# tally_box.net
KiCad netlist of a schematic drawn in EAGLE
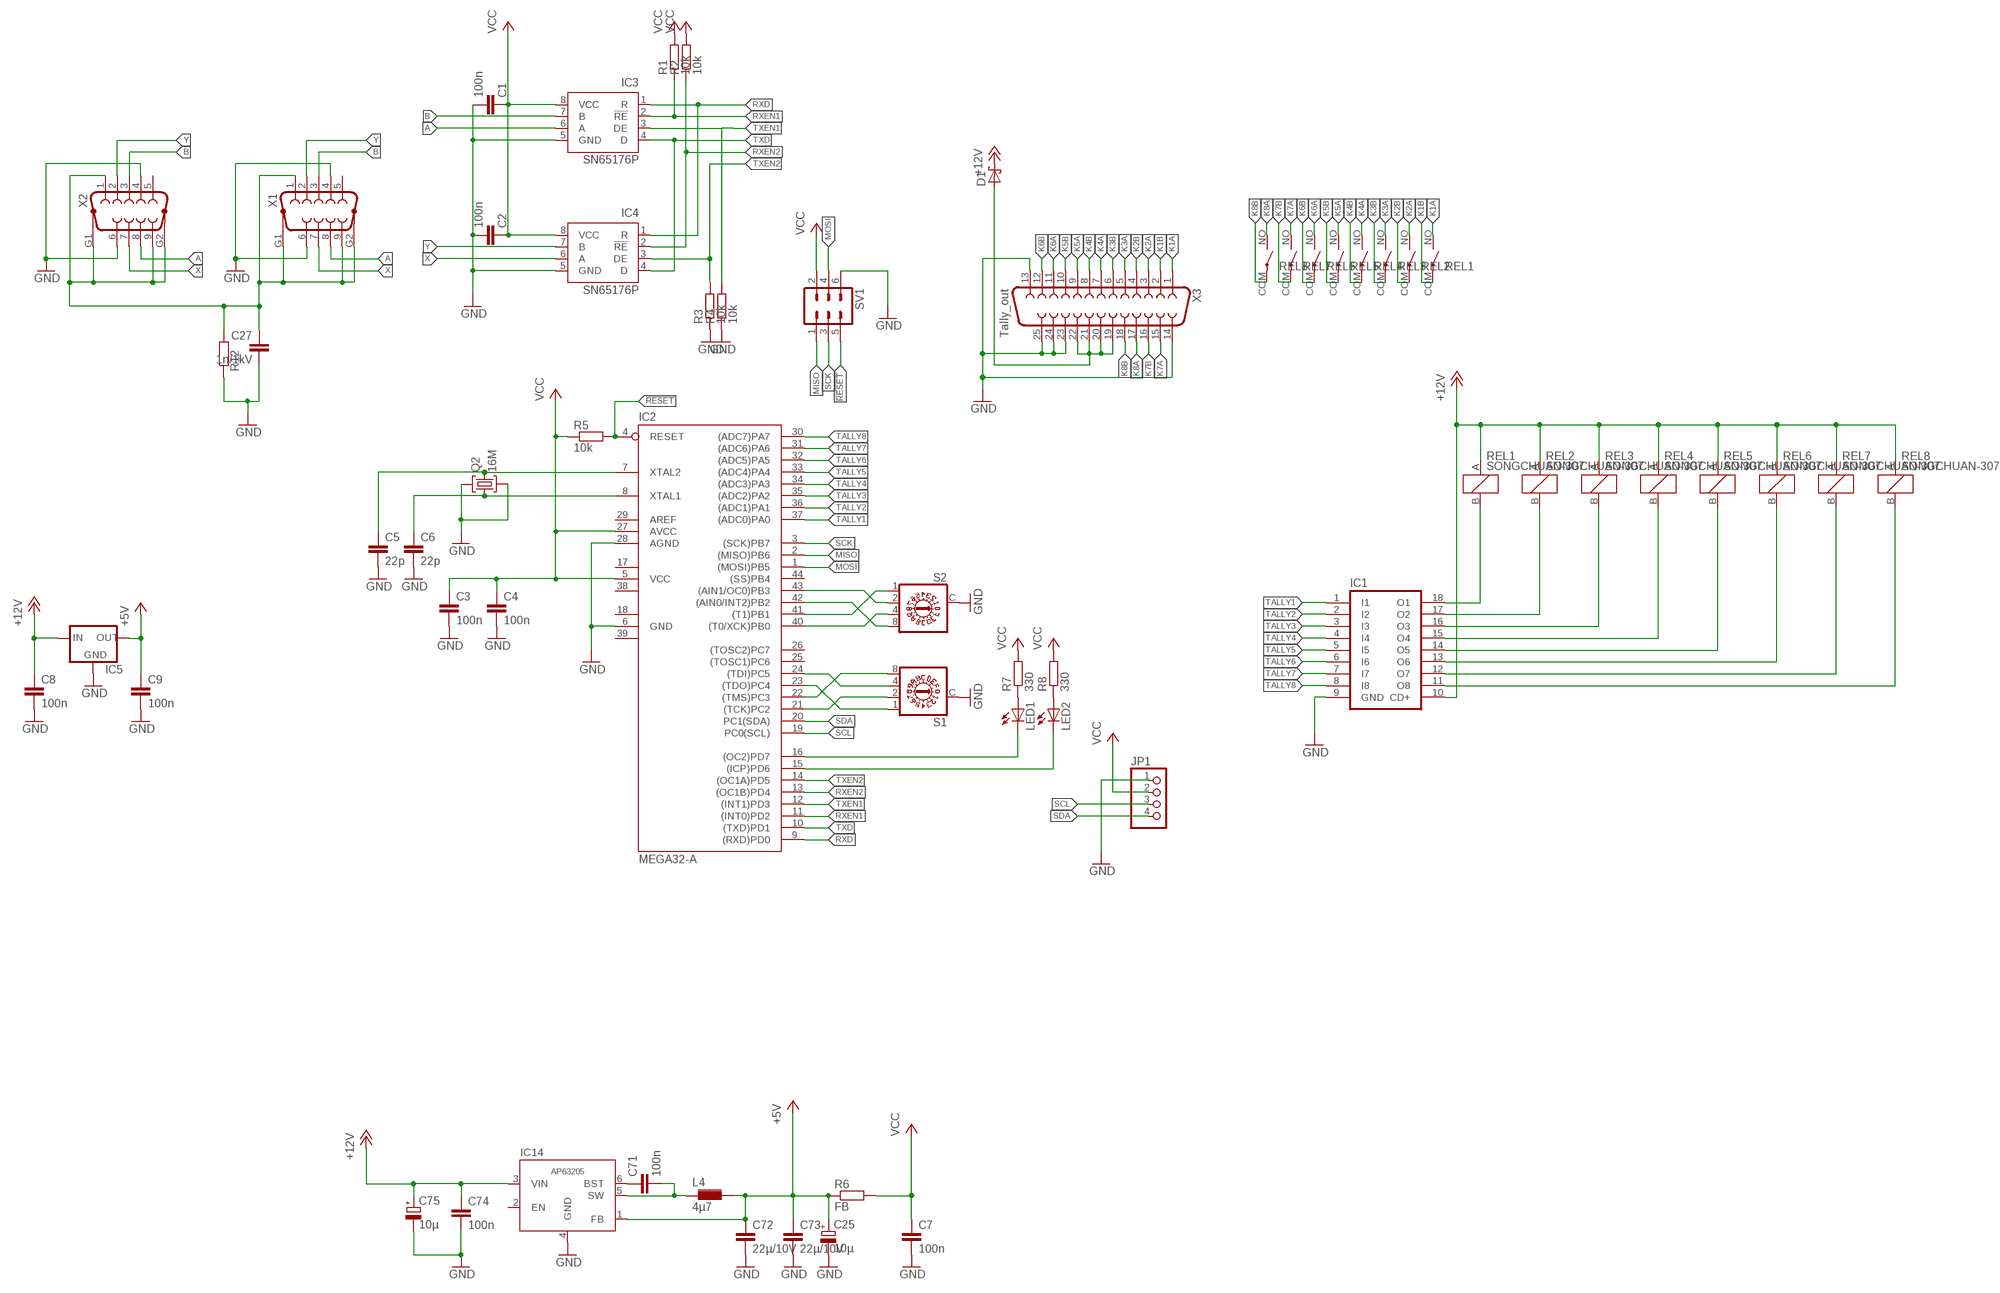
[diagram p0: schematic, sheet 1]

(export (version "E")
  (design (tool "Eeschema 10.0.6"))
  (components
    (comp (ref "C1")
      (value "100n")
      (footprint "eagle-import:C0603")
      (libsource (lib "eagle-import") (part "C-EUC0603"))
    )
    (comp (ref "C2")
      (value "100n")
      (footprint "eagle-import:C0603")
      (libsource (lib "eagle-import") (part "C-EUC0603"))
    )
    (comp (ref "C3")
      (value "100n")
      (footprint "eagle-import:C0603")
      (libsource (lib "eagle-import") (part "C-EUC0603"))
    )
    (comp (ref "C4")
      (value "100n")
      (footprint "eagle-import:C0603")
      (libsource (lib "eagle-import") (part "C-EUC0603"))
    )
    (comp (ref "C5")
      (value "22p")
      (footprint "eagle-import:C0603")
      (libsource (lib "eagle-import") (part "C-EUC0603"))
    )
    (comp (ref "C6")
      (value "22p")
      (footprint "eagle-import:C0603")
      (libsource (lib "eagle-import") (part "C-EUC0603"))
    )
    (comp (ref "C7")
      (value "100n")
      (footprint "eagle-import:C0603")
      (libsource (lib "eagle-import") (part "C-EUC0603"))
    )
    (comp (ref "C8")
      (value "100n")
      (footprint "eagle-import:C0805")
      (libsource (lib "eagle-import") (part "C-EUC0805"))
    )
    (comp (ref "C9")
      (value "100n")
      (footprint "eagle-import:C0805")
      (libsource (lib "eagle-import") (part "C-EUC0805"))
    )
    (comp (ref "C25")
      (value "10µ")
      (footprint "eagle-import:PANASONIC_C")
      (libsource (lib "eagle-import") (part "CPOL-EUC"))
    )
    (comp (ref "C27")
      (value "1n/1kV")
      (footprint "eagle-import:C1206")
      (libsource (lib "eagle-import") (part "C-EUC1206"))
    )
    (comp (ref "C71")
      (value "100n")
      (footprint "eagle-import:C0805")
      (libsource (lib "eagle-import") (part "C-EUC0805"))
    )
    (comp (ref "C72")
      (value "22µ/10V")
      (footprint "eagle-import:C0805")
      (libsource (lib "eagle-import") (part "C-EUC0805"))
    )
    (comp (ref "C73")
      (value "22µ/10V")
      (footprint "eagle-import:C0805")
      (libsource (lib "eagle-import") (part "C-EUC0805"))
    )
    (comp (ref "C74")
      (value "100n")
      (footprint "eagle-import:C0805")
      (libsource (lib "eagle-import") (part "C-EUC0805"))
    )
    (comp (ref "C75")
      (value "10µ")
      (footprint "eagle-import:PANASONIC_D")
      (libsource (lib "eagle-import") (part "CPOL-EUD"))
    )
    (comp (ref "D1")
      (value "SCHOTTKY-DIODESMD")
      (footprint "eagle-import:SMB")
      (libsource (lib "eagle-import") (part "SCHOTTKY-DIODESMD"))
    )
    (comp (ref "IC1")
      (value "ULN2803A")
      (footprint "eagle-import:DIL18")
      (libsource (lib "eagle-import") (part "ULN2803A"))
    )
    (comp (ref "IC2")
      (value "MEGA32-A")
      (footprint "eagle-import:TQFP44")
      (libsource (lib "eagle-import") (part "MEGA32-A"))
    )
    (comp (ref "IC3")
      (value "SN65176P")
      (footprint "eagle-import:DIL08")
      (libsource (lib "eagle-import") (part "SN65176P"))
    )
    (comp (ref "IC4")
      (value "SN65176P")
      (footprint "eagle-import:DIL08")
      (libsource (lib "eagle-import") (part "SN65176P"))
    )
    (comp (ref "IC5")
      (value "78XXS")
      (footprint "eagle-import:78XXS")
      (libsource (lib "eagle-import") (part "78XXS"))
    )
    (comp (ref "IC14")
      (value "AP63205")
      (footprint "eagle-import:SOT23-6L")
      (libsource (lib "eagle-import") (part "AP6320X"))
    )
    (comp (ref "JP1")
      (value "PINHD-1X4")
      (footprint "eagle-import:1X04")
      (libsource (lib "eagle-import") (part "PINHD-1X4"))
    )
    (comp (ref "L4")
      (value "4µ7")
      (footprint "eagle-import:TYA4020")
      (libsource (lib "eagle-import") (part "L-TYA4020"))
    )
    (comp (ref "LED1")
      (value "LED-TOPLED")
      (footprint "eagle-import:P-LCC-2")
      (libsource (lib "eagle-import") (part "LED-TOPLED"))
    )
    (comp (ref "LED2")
      (value "LED-TOPLED")
      (footprint "eagle-import:P-LCC-2")
      (libsource (lib "eagle-import") (part "LED-TOPLED"))
    )
    (comp (ref "Q2")
      (value "16M")
      (footprint "eagle-import:MJ")
      (libsource (lib "eagle-import") (part "CRYSTAL_SHIELDEDMJ"))
    )
    (comp (ref "R1")
      (value "10k")
      (footprint "eagle-import:R0603")
      (libsource (lib "eagle-import") (part "R-EU_R0603"))
    )
    (comp (ref "R2")
      (value "10k")
      (footprint "eagle-import:R0603")
      (libsource (lib "eagle-import") (part "R-EU_R0603"))
    )
    (comp (ref "R3")
      (value "10k")
      (footprint "eagle-import:R0603")
      (libsource (lib "eagle-import") (part "R-EU_R0603"))
    )
    (comp (ref "R4")
      (value "10k")
      (footprint "eagle-import:R0603")
      (libsource (lib "eagle-import") (part "R-EU_R0603"))
    )
    (comp (ref "R5")
      (value "10k")
      (footprint "eagle-import:R0603")
      (libsource (lib "eagle-import") (part "R-EU_R0603"))
    )
    (comp (ref "R6")
      (value "FB")
      (footprint "eagle-import:R0805")
      (libsource (lib "eagle-import") (part "R-EU_R0805"))
    )
    (comp (ref "R7")
      (value "330")
      (footprint "eagle-import:R0603")
      (libsource (lib "eagle-import") (part "R-EU_R0603"))
    )
    (comp (ref "R8")
      (value "330")
      (footprint "eagle-import:R0603")
      (libsource (lib "eagle-import") (part "R-EU_R0603"))
    )
    (comp (ref "R12")
      (value "R-EU_R0603")
      (footprint "eagle-import:R0603")
      (libsource (lib "eagle-import") (part "R-EU_R0603"))
    )
    (comp (ref "REL1")
      (value "SONGCHUAN-307")
      (footprint "eagle-import:SONCHUAN-307")
      (libsource (lib "eagle-import") (part "SONGCHUAN-307"))
    )
    (comp (ref "REL2")
      (value "SONGCHUAN-307")
      (footprint "eagle-import:SONCHUAN-307")
      (libsource (lib "eagle-import") (part "SONGCHUAN-307"))
    )
    (comp (ref "REL3")
      (value "SONGCHUAN-307")
      (footprint "eagle-import:SONCHUAN-307")
      (libsource (lib "eagle-import") (part "SONGCHUAN-307"))
    )
    (comp (ref "REL4")
      (value "SONGCHUAN-307")
      (footprint "eagle-import:SONCHUAN-307")
      (libsource (lib "eagle-import") (part "SONGCHUAN-307"))
    )
    (comp (ref "REL5")
      (value "SONGCHUAN-307")
      (footprint "eagle-import:SONCHUAN-307")
      (libsource (lib "eagle-import") (part "SONGCHUAN-307"))
    )
    (comp (ref "REL6")
      (value "SONGCHUAN-307")
      (footprint "eagle-import:SONCHUAN-307")
      (libsource (lib "eagle-import") (part "SONGCHUAN-307"))
    )
    (comp (ref "REL7")
      (value "SONGCHUAN-307")
      (footprint "eagle-import:SONCHUAN-307")
      (libsource (lib "eagle-import") (part "SONGCHUAN-307"))
    )
    (comp (ref "REL8")
      (value "SONGCHUAN-307")
      (footprint "eagle-import:SONCHUAN-307")
      (libsource (lib "eagle-import") (part "SONGCHUAN-307"))
    )
    (comp (ref "S1")
      (value "A1353HEX")
      (footprint "eagle-import:A1353HEX")
      (libsource (lib "eagle-import") (part "A1353HEX"))
    )
    (comp (ref "S2")
      (value "A1353HEX")
      (footprint "eagle-import:A1353HEX")
      (libsource (lib "eagle-import") (part "A1353HEX"))
    )
    (comp (ref "SV1")
      (value "ML6")
      (footprint "eagle-import:ML6")
      (libsource (lib "eagle-import") (part "ML6"))
    )
    (comp (ref "X1")
      (value "F09HP")
      (footprint "eagle-import:F09HP")
      (libsource (lib "eagle-import") (part "F09HP"))
    )
    (comp (ref "X2")
      (value "F09HP")
      (footprint "eagle-import:F09HP")
      (libsource (lib "eagle-import") (part "F09HP"))
    )
    (comp (ref "X3")
      (value "Tally_out")
      (footprint "eagle-import:F25HP")
      (libsource (lib "eagle-import") (part "F25HP"))
    )
  )
  (nets
    (net (code "1") (name "+5V") (class "Default")
      (node (ref "C25") (pin "+") (pinfunction "+_+") (pintype "passive"))
      (node (ref "C72") (pin "1") (pinfunction "1_1") (pintype "passive"))
      (node (ref "C73") (pin "1") (pinfunction "1_1") (pintype "passive"))
      (node (ref "C9") (pin "1") (pinfunction "1_1") (pintype "passive"))
      (node (ref "IC14") (pin "1") (pinfunction "FB_1") (pintype "passive"))
      (node (ref "IC5") (pin "OUT") (pinfunction "OUT_OUT") (pintype "passive"))
      (node (ref "L4") (pin "2") (pinfunction "P$2_2") (pintype "passive"))
      (node (ref "R6") (pin "1") (pinfunction "1_1") (pintype "passive"))
    )
    (net (code "2") (name "+12V") (class "Default")
      (node (ref "C74") (pin "1") (pinfunction "1_1") (pintype "passive"))
      (node (ref "C75") (pin "+") (pinfunction "+_+") (pintype "passive"))
      (node (ref "C8") (pin "1") (pinfunction "1_1") (pintype "passive"))
      (node (ref "D1") (pin "C") (pinfunction "C_C") (pintype "passive"))
      (node (ref "IC1") (pin "10") (pinfunction "CD+_10") (pintype "passive"))
      (node (ref "IC14") (pin "3") (pinfunction "VIN_3") (pintype "power_in"))
      (node (ref "IC5") (pin "IN") (pinfunction "IN_IN") (pintype "input"))
      (node (ref "REL1") (pin "A") (pinfunction "+_A") (pintype "passive"))
      (node (ref "REL2") (pin "A") (pinfunction "+_A") (pintype "passive"))
      (node (ref "REL3") (pin "A") (pinfunction "+_A") (pintype "passive"))
      (node (ref "REL4") (pin "A") (pinfunction "+_A") (pintype "passive"))
      (node (ref "REL5") (pin "A") (pinfunction "+_A") (pintype "passive"))
      (node (ref "REL6") (pin "A") (pinfunction "+_A") (pintype "passive"))
      (node (ref "REL7") (pin "A") (pinfunction "+_A") (pintype "passive"))
      (node (ref "REL8") (pin "A") (pinfunction "+_A") (pintype "passive"))
    )
    (net (code "3") (name "/AREF") (class "Default")
      (node (ref "IC2") (pin "29") (pinfunction "AREF_29") (pintype "power_in"))
    )
    (net (code "4") (name "/GND1") (class "Default")
      (node (ref "IC2") (pin "18") (pinfunction "GND1_18") (pintype "power_in"))
    )
    (net (code "5") (name "/GND2") (class "Default")
      (node (ref "IC2") (pin "39") (pinfunction "GND2_39") (pintype "power_in"))
    )
    (net (code "6") (name "/VCC1") (class "Default")
      (node (ref "IC2") (pin "17") (pinfunction "VCC1_17") (pintype "power_in"))
    )
    (net (code "7") (name "/VCC2") (class "Default")
      (node (ref "IC2") (pin "38") (pinfunction "VCC2_38") (pintype "power_in"))
    )
    (net (code "8") (name "/~{RESET}") (class "Default")
      (node (ref "IC2") (pin "4") (pinfunction "RESET_4") (pintype "input"))
      (node (ref "R5") (pin "2") (pinfunction "2_2") (pintype "passive"))
      (node (ref "SV1") (pin "5") (pinfunction "5_5") (pintype "passive"))
    )
    (net (code "9") (name "A") (class "Default")
      (node (ref "IC3") (pin "6") (pinfunction "A_6") (pintype "input"))
      (node (ref "X1") (pin "8") (pinfunction "8_8") (pintype "passive"))
      (node (ref "X2") (pin "8") (pinfunction "8_8") (pintype "passive"))
    )
    (net (code "10") (name "B") (class "Default")
      (node (ref "IC3") (pin "7") (pinfunction "B_7") (pintype "input"))
      (node (ref "X1") (pin "3") (pinfunction "3_3") (pintype "passive"))
      (node (ref "X2") (pin "3") (pinfunction "3_3") (pintype "passive"))
    )
    (net (code "11") (name "GND") (class "Default")
      (node (ref "C1") (pin "2") (pinfunction "2_2") (pintype "passive"))
      (node (ref "C2") (pin "2") (pinfunction "2_2") (pintype "passive"))
      (node (ref "C25") (pin "-") (pinfunction "-_-") (pintype "passive"))
      (node (ref "C27") (pin "2") (pinfunction "2_2") (pintype "passive"))
      (node (ref "C3") (pin "2") (pinfunction "2_2") (pintype "passive"))
      (node (ref "C4") (pin "2") (pinfunction "2_2") (pintype "passive"))
      (node (ref "C5") (pin "2") (pinfunction "2_2") (pintype "passive"))
      (node (ref "C6") (pin "2") (pinfunction "2_2") (pintype "passive"))
      (node (ref "C7") (pin "2") (pinfunction "2_2") (pintype "passive"))
      (node (ref "C72") (pin "2") (pinfunction "2_2") (pintype "passive"))
      (node (ref "C73") (pin "2") (pinfunction "2_2") (pintype "passive"))
      (node (ref "C74") (pin "2") (pinfunction "2_2") (pintype "passive"))
      (node (ref "C75") (pin "-") (pinfunction "-_-") (pintype "passive"))
      (node (ref "C8") (pin "2") (pinfunction "2_2") (pintype "passive"))
      (node (ref "C9") (pin "2") (pinfunction "2_2") (pintype "passive"))
      (node (ref "IC1") (pin "9") (pinfunction "GND_9") (pintype "power_in"))
      (node (ref "IC14") (pin "4") (pinfunction "GND_4") (pintype "power_in"))
      (node (ref "IC2") (pin "28") (pinfunction "AGND_28") (pintype "power_in"))
      (node (ref "IC2") (pin "6") (pinfunction "GND_6") (pintype "power_in"))
      (node (ref "IC3") (pin "5") (pinfunction "GND_5") (pintype "input"))
      (node (ref "IC4") (pin "5") (pinfunction "GND_5") (pintype "input"))
      (node (ref "IC5") (pin "GND") (pinfunction "GND_GND") (pintype "input"))
      (node (ref "JP1") (pin "1") (pinfunction "1_1") (pintype "passive"))
      (node (ref "Q2") (pin "2") (pinfunction "G1_2") (pintype "passive"))
      (node (ref "Q2") (pin "4") (pinfunction "G2_4") (pintype "passive"))
      (node (ref "R12") (pin "1") (pinfunction "1_1") (pintype "passive"))
      (node (ref "R3") (pin "1") (pinfunction "1_1") (pintype "passive"))
      (node (ref "R4") (pin "1") (pinfunction "1_1") (pintype "passive"))
      (node (ref "S1") (pin "C") (pinfunction "C_C") (pintype "passive"))
      (node (ref "S2") (pin "C") (pinfunction "C_C") (pintype "passive"))
      (node (ref "SV1") (pin "6") (pinfunction "6_6") (pintype "passive"))
      (node (ref "X1") (pin "4") (pinfunction "4_4") (pintype "passive"))
      (node (ref "X1") (pin "6") (pinfunction "6_6") (pintype "passive"))
      (node (ref "X2") (pin "4") (pinfunction "4_4") (pintype "passive"))
      (node (ref "X2") (pin "6") (pinfunction "6_6") (pintype "passive"))
      (node (ref "X3") (pin "13") (pinfunction "13_13") (pintype "passive"))
      (node (ref "X3") (pin "14") (pinfunction "14_14") (pintype "passive"))
      (node (ref "X3") (pin "23") (pinfunction "23_23") (pintype "passive"))
      (node (ref "X3") (pin "24") (pinfunction "24_24") (pintype "passive"))
      (node (ref "X3") (pin "25") (pinfunction "25_25") (pintype "passive"))
    )
    (net (code "12") (name "K1A") (class "Default")
      (node (ref "REL1") (pin "NO") (pinfunction "S_NO") (pintype "passive"))
      (node (ref "X3") (pin "1") (pinfunction "1_1") (pintype "passive"))
    )
    (net (code "13") (name "K1B") (class "Default")
      (node (ref "REL1") (pin "COM") (pinfunction "P_COM") (pintype "passive"))
      (node (ref "X3") (pin "2") (pinfunction "2_2") (pintype "passive"))
    )
    (net (code "14") (name "K2A") (class "Default")
      (node (ref "REL2") (pin "NO") (pinfunction "S_NO") (pintype "passive"))
      (node (ref "X3") (pin "3") (pinfunction "3_3") (pintype "passive"))
    )
    (net (code "15") (name "K2B") (class "Default")
      (node (ref "REL2") (pin "COM") (pinfunction "P_COM") (pintype "passive"))
      (node (ref "X3") (pin "4") (pinfunction "4_4") (pintype "passive"))
    )
    (net (code "16") (name "K3A") (class "Default")
      (node (ref "REL3") (pin "NO") (pinfunction "S_NO") (pintype "passive"))
      (node (ref "X3") (pin "5") (pinfunction "5_5") (pintype "passive"))
    )
    (net (code "17") (name "K3B") (class "Default")
      (node (ref "REL3") (pin "COM") (pinfunction "P_COM") (pintype "passive"))
      (node (ref "X3") (pin "6") (pinfunction "6_6") (pintype "passive"))
    )
    (net (code "18") (name "K4A") (class "Default")
      (node (ref "REL4") (pin "NO") (pinfunction "S_NO") (pintype "passive"))
      (node (ref "X3") (pin "7") (pinfunction "7_7") (pintype "passive"))
    )
    (net (code "19") (name "K4B") (class "Default")
      (node (ref "REL4") (pin "COM") (pinfunction "P_COM") (pintype "passive"))
      (node (ref "X3") (pin "8") (pinfunction "8_8") (pintype "passive"))
    )
    (net (code "20") (name "K5A") (class "Default")
      (node (ref "REL5") (pin "NO") (pinfunction "S_NO") (pintype "passive"))
      (node (ref "X3") (pin "9") (pinfunction "9_9") (pintype "passive"))
    )
    (net (code "21") (name "K5B") (class "Default")
      (node (ref "REL5") (pin "COM") (pinfunction "P_COM") (pintype "passive"))
      (node (ref "X3") (pin "10") (pinfunction "10_10") (pintype "passive"))
    )
    (net (code "22") (name "K6A") (class "Default")
      (node (ref "REL6") (pin "NO") (pinfunction "S_NO") (pintype "passive"))
      (node (ref "X3") (pin "11") (pinfunction "11_11") (pintype "passive"))
    )
    (net (code "23") (name "K6B") (class "Default")
      (node (ref "REL6") (pin "COM") (pinfunction "P_COM") (pintype "passive"))
      (node (ref "X3") (pin "12") (pinfunction "12_12") (pintype "passive"))
    )
    (net (code "24") (name "K7A") (class "Default")
      (node (ref "REL7") (pin "NO") (pinfunction "S_NO") (pintype "passive"))
      (node (ref "X3") (pin "15") (pinfunction "15_15") (pintype "passive"))
    )
    (net (code "25") (name "K7B") (class "Default")
      (node (ref "REL7") (pin "COM") (pinfunction "P_COM") (pintype "passive"))
      (node (ref "X3") (pin "16") (pinfunction "16_16") (pintype "passive"))
    )
    (net (code "26") (name "K8A") (class "Default")
      (node (ref "REL8") (pin "NO") (pinfunction "S_NO") (pintype "passive"))
      (node (ref "X3") (pin "17") (pinfunction "17_17") (pintype "passive"))
    )
    (net (code "27") (name "K8B") (class "Default")
      (node (ref "REL8") (pin "COM") (pinfunction "P_COM") (pintype "passive"))
      (node (ref "X3") (pin "18") (pinfunction "18_18") (pintype "passive"))
    )
    (net (code "28") (name "MISO") (class "Default")
      (node (ref "IC2") (pin "2") (pinfunction "(MISO)PB6_2") (pintype "bidirectional"))
      (node (ref "SV1") (pin "1") (pinfunction "1_1") (pintype "passive"))
    )
    (net (code "29") (name "MOSI") (class "Default")
      (node (ref "IC2") (pin "1") (pinfunction "(MOSI)PB5_1") (pintype "bidirectional"))
      (node (ref "SV1") (pin "4") (pinfunction "4_4") (pintype "passive"))
    )
    (net (code "30") (name "Net-(C27-Pad1)") (class "Default")
      (node (ref "C27") (pin "1") (pinfunction "1_1") (pintype "passive"))
      (node (ref "R12") (pin "2") (pinfunction "2_2") (pintype "passive"))
      (node (ref "X1") (pin "1") (pinfunction "1_1") (pintype "passive"))
      (node (ref "X1") (pin "9") (pinfunction "9_9") (pintype "passive"))
      (node (ref "X1") (pin "G1") (pinfunction "G1_G1") (pintype "passive"))
      (node (ref "X1") (pin "G2") (pinfunction "G2_G2") (pintype "passive"))
      (node (ref "X2") (pin "1") (pinfunction "1_1") (pintype "passive"))
      (node (ref "X2") (pin "9") (pinfunction "9_9") (pintype "passive"))
      (node (ref "X2") (pin "G1") (pinfunction "G1_G1") (pintype "passive"))
      (node (ref "X2") (pin "G2") (pinfunction "G2_G2") (pintype "passive"))
    )
    (net (code "31") (name "Net-(D1-PadA)") (class "Default")
      (node (ref "D1") (pin "A") (pinfunction "A_A") (pintype "passive"))
      (node (ref "X3") (pin "19") (pinfunction "19_19") (pintype "passive"))
      (node (ref "X3") (pin "20") (pinfunction "20_20") (pintype "passive"))
      (node (ref "X3") (pin "21") (pinfunction "21_21") (pintype "passive"))
      (node (ref "X3") (pin "22") (pinfunction "22_22") (pintype "passive"))
    )
    (net (code "32") (name "Net-(IC1-O1)") (class "Default")
      (node (ref "IC1") (pin "18") (pinfunction "O1_18") (pintype "open_collector"))
      (node (ref "REL1") (pin "B") (pinfunction "-_B") (pintype "passive"))
    )
    (net (code "33") (name "Net-(IC1-O2)") (class "Default")
      (node (ref "IC1") (pin "17") (pinfunction "O2_17") (pintype "open_collector"))
      (node (ref "REL2") (pin "B") (pinfunction "-_B") (pintype "passive"))
    )
    (net (code "34") (name "Net-(IC1-O3)") (class "Default")
      (node (ref "IC1") (pin "16") (pinfunction "O3_16") (pintype "open_collector"))
      (node (ref "REL3") (pin "B") (pinfunction "-_B") (pintype "passive"))
    )
    (net (code "35") (name "Net-(IC1-O4)") (class "Default")
      (node (ref "IC1") (pin "15") (pinfunction "O4_15") (pintype "open_collector"))
      (node (ref "REL4") (pin "B") (pinfunction "-_B") (pintype "passive"))
    )
    (net (code "36") (name "Net-(IC1-O5)") (class "Default")
      (node (ref "IC1") (pin "14") (pinfunction "O5_14") (pintype "open_collector"))
      (node (ref "REL5") (pin "B") (pinfunction "-_B") (pintype "passive"))
    )
    (net (code "37") (name "Net-(IC1-O6)") (class "Default")
      (node (ref "IC1") (pin "13") (pinfunction "O6_13") (pintype "open_collector"))
      (node (ref "REL6") (pin "B") (pinfunction "-_B") (pintype "passive"))
    )
    (net (code "38") (name "Net-(IC1-O7)") (class "Default")
      (node (ref "IC1") (pin "12") (pinfunction "O7_12") (pintype "open_collector"))
      (node (ref "REL7") (pin "B") (pinfunction "-_B") (pintype "passive"))
    )
    (net (code "39") (name "Net-(IC1-O8)") (class "Default")
      (node (ref "IC1") (pin "11") (pinfunction "O8_11") (pintype "open_collector"))
      (node (ref "REL8") (pin "B") (pinfunction "-_B") (pintype "passive"))
    )
    (net (code "40") (name "Net-(IC2-(AIN0{slash}INT2)PB2)") (class "Default")
      (node (ref "IC2") (pin "42") (pinfunction "(AIN0/INT2)PB2_42") (pintype "bidirectional"))
      (node (ref "S2") (pin "8") (pinfunction "8_8") (pintype "passive"))
    )
    (net (code "41") (name "Net-(IC2-(AIN1{slash}OC0)PB3)") (class "Default")
      (node (ref "IC2") (pin "43") (pinfunction "(AIN1/OC0)PB3_43") (pintype "bidirectional"))
      (node (ref "S2") (pin "2") (pinfunction "2_2") (pintype "passive"))
    )
    (net (code "42") (name "Net-(IC2-(ICP)PD6)") (class "Default")
      (node (ref "IC2") (pin "15") (pinfunction "(ICP)PD6_15") (pintype "bidirectional"))
      (node (ref "LED2") (pin "C") (pinfunction "C_C") (pintype "passive"))
    )
    (net (code "43") (name "Net-(IC2-(OC2)PD7)") (class "Default")
      (node (ref "IC2") (pin "16") (pinfunction "(OC2)PD7_16") (pintype "bidirectional"))
      (node (ref "LED1") (pin "C") (pinfunction "C_C") (pintype "passive"))
    )
    (net (code "44") (name "Net-(IC2-(T0{slash}XCK)PB0)") (class "Default")
      (node (ref "IC2") (pin "40") (pinfunction "(T0/XCK)PB0_40") (pintype "bidirectional"))
      (node (ref "S2") (pin "4") (pinfunction "4_4") (pintype "passive"))
    )
    (net (code "45") (name "Net-(IC2-(T1)PB1)") (class "Default")
      (node (ref "IC2") (pin "41") (pinfunction "(T1)PB1_41") (pintype "bidirectional"))
      (node (ref "S2") (pin "1") (pinfunction "1_1") (pintype "passive"))
    )
    (net (code "46") (name "Net-(IC2-(TCK)PC2)") (class "Default")
      (node (ref "IC2") (pin "21") (pinfunction "(TCK)PC2_21") (pintype "bidirectional"))
      (node (ref "S1") (pin "2") (pinfunction "2_2") (pintype "passive"))
    )
    (net (code "47") (name "Net-(IC2-(TDI)PC5)") (class "Default")
      (node (ref "IC2") (pin "24") (pinfunction "(TDI)PC5_24") (pintype "bidirectional"))
      (node (ref "S1") (pin "4") (pinfunction "4_4") (pintype "passive"))
    )
    (net (code "48") (name "Net-(IC2-(TDO)PC4)") (class "Default")
      (node (ref "IC2") (pin "23") (pinfunction "(TDO)PC4_23") (pintype "bidirectional"))
      (node (ref "S1") (pin "1") (pinfunction "1_1") (pintype "passive"))
    )
    (net (code "49") (name "Net-(IC2-(TMS)PC3)") (class "Default")
      (node (ref "IC2") (pin "22") (pinfunction "(TMS)PC3_22") (pintype "bidirectional"))
      (node (ref "S1") (pin "8") (pinfunction "8_8") (pintype "passive"))
    )
    (net (code "50") (name "Net-(IC2-XTAL1)") (class "Default")
      (node (ref "C6") (pin "1") (pinfunction "1_1") (pintype "passive"))
      (node (ref "IC2") (pin "8") (pinfunction "XTAL1_8") (pintype "bidirectional"))
      (node (ref "Q2") (pin "1") (pinfunction "1_1") (pintype "passive"))
    )
    (net (code "51") (name "Net-(IC2-XTAL2)") (class "Default")
      (node (ref "C5") (pin "1") (pinfunction "1_1") (pintype "passive"))
      (node (ref "IC2") (pin "7") (pinfunction "XTAL2_7") (pintype "bidirectional"))
      (node (ref "Q2") (pin "3") (pinfunction "2_3") (pintype "passive"))
    )
    (net (code "52") (name "Net-(IC14-BST)") (class "Default")
      (node (ref "C71") (pin "1") (pinfunction "1_1") (pintype "passive"))
      (node (ref "IC14") (pin "6") (pinfunction "BST_6") (pintype "passive"))
    )
    (net (code "53") (name "Net-(IC14-SW)") (class "Default")
      (node (ref "C71") (pin "2") (pinfunction "2_2") (pintype "passive"))
      (node (ref "IC14") (pin "5") (pinfunction "SW_5") (pintype "output"))
      (node (ref "L4") (pin "1") (pinfunction "P$1_1") (pintype "passive"))
    )
    (net (code "54") (name "Net-(LED1-PadA)") (class "Default")
      (node (ref "LED1") (pin "A") (pinfunction "A_A") (pintype "passive"))
      (node (ref "R7") (pin "1") (pinfunction "1_1") (pintype "passive"))
    )
    (net (code "55") (name "Net-(LED2-PadA)") (class "Default")
      (node (ref "LED2") (pin "A") (pinfunction "A_A") (pintype "passive"))
      (node (ref "R8") (pin "1") (pinfunction "1_1") (pintype "passive"))
    )
    (net (code "56") (name "RXD") (class "Default")
      (node (ref "IC2") (pin "9") (pinfunction "(RXD)PD0_9") (pintype "bidirectional"))
      (node (ref "IC3") (pin "1") (pinfunction "R_1") (pintype "input"))
      (node (ref "IC4") (pin "1") (pinfunction "R_1") (pintype "input"))
    )
    (net (code "57") (name "RXEN1") (class "Default")
      (node (ref "IC2") (pin "11") (pinfunction "(INT0)PD2_11") (pintype "bidirectional"))
      (node (ref "IC3") (pin "2") (pinfunction "~{RE}_2") (pintype "input"))
      (node (ref "R1") (pin "1") (pinfunction "1_1") (pintype "passive"))
    )
    (net (code "58") (name "RXEN2") (class "Default")
      (node (ref "IC2") (pin "13") (pinfunction "(OC1B)PD4_13") (pintype "bidirectional"))
      (node (ref "IC4") (pin "2") (pinfunction "~{RE}_2") (pintype "input"))
      (node (ref "R2") (pin "1") (pinfunction "1_1") (pintype "passive"))
    )
    (net (code "59") (name "SCK") (class "Default")
      (node (ref "IC2") (pin "3") (pinfunction "(SCK)PB7_3") (pintype "bidirectional"))
      (node (ref "SV1") (pin "3") (pinfunction "3_3") (pintype "passive"))
    )
    (net (code "60") (name "SCL") (class "Default")
      (node (ref "IC2") (pin "19") (pinfunction "PC0(SCL)_19") (pintype "bidirectional"))
      (node (ref "JP1") (pin "3") (pinfunction "3_3") (pintype "passive"))
    )
    (net (code "61") (name "SDA") (class "Default")
      (node (ref "IC2") (pin "20") (pinfunction "PC1(SDA)_20") (pintype "bidirectional"))
      (node (ref "JP1") (pin "4") (pinfunction "4_4") (pintype "passive"))
    )
    (net (code "62") (name "TALLY1") (class "Default")
      (node (ref "IC1") (pin "1") (pinfunction "I1_1") (pintype "input"))
      (node (ref "IC2") (pin "37") (pinfunction "(ADC0)PA0_37") (pintype "bidirectional"))
    )
    (net (code "63") (name "TALLY2") (class "Default")
      (node (ref "IC1") (pin "2") (pinfunction "I2_2") (pintype "input"))
      (node (ref "IC2") (pin "36") (pinfunction "(ADC1)PA1_36") (pintype "bidirectional"))
    )
    (net (code "64") (name "TALLY3") (class "Default")
      (node (ref "IC1") (pin "3") (pinfunction "I3_3") (pintype "input"))
      (node (ref "IC2") (pin "35") (pinfunction "(ADC2)PA2_35") (pintype "bidirectional"))
    )
    (net (code "65") (name "TALLY4") (class "Default")
      (node (ref "IC1") (pin "4") (pinfunction "I4_4") (pintype "input"))
      (node (ref "IC2") (pin "34") (pinfunction "(ADC3)PA3_34") (pintype "bidirectional"))
    )
    (net (code "66") (name "TALLY5") (class "Default")
      (node (ref "IC1") (pin "5") (pinfunction "I5_5") (pintype "input"))
      (node (ref "IC2") (pin "33") (pinfunction "(ADC4)PA4_33") (pintype "bidirectional"))
    )
    (net (code "67") (name "TALLY6") (class "Default")
      (node (ref "IC1") (pin "6") (pinfunction "I6_6") (pintype "input"))
      (node (ref "IC2") (pin "32") (pinfunction "(ADC5)PA5_32") (pintype "bidirectional"))
    )
    (net (code "68") (name "TALLY7") (class "Default")
      (node (ref "IC1") (pin "7") (pinfunction "I7_7") (pintype "input"))
      (node (ref "IC2") (pin "31") (pinfunction "(ADC6)PA6_31") (pintype "bidirectional"))
    )
    (net (code "69") (name "TALLY8") (class "Default")
      (node (ref "IC1") (pin "8") (pinfunction "I8_8") (pintype "input"))
      (node (ref "IC2") (pin "30") (pinfunction "(ADC7)PA7_30") (pintype "bidirectional"))
    )
    (net (code "70") (name "TXD") (class "Default")
      (node (ref "IC2") (pin "10") (pinfunction "(TXD)PD1_10") (pintype "bidirectional"))
      (node (ref "IC3") (pin "4") (pinfunction "D_4") (pintype "input"))
      (node (ref "IC4") (pin "4") (pinfunction "D_4") (pintype "input"))
    )
    (net (code "71") (name "TXEN1") (class "Default")
      (node (ref "IC2") (pin "12") (pinfunction "(INT1)PD3_12") (pintype "bidirectional"))
      (node (ref "IC3") (pin "3") (pinfunction "DE_3") (pintype "input"))
      (node (ref "R4") (pin "2") (pinfunction "2_2") (pintype "passive"))
    )
    (net (code "72") (name "TXEN2") (class "Default")
      (node (ref "IC2") (pin "14") (pinfunction "(OC1A)PD5_14") (pintype "bidirectional"))
      (node (ref "IC4") (pin "3") (pinfunction "DE_3") (pintype "input"))
      (node (ref "R3") (pin "2") (pinfunction "2_2") (pintype "passive"))
    )
    (net (code "73") (name "VCC") (class "Default")
      (node (ref "C1") (pin "1") (pinfunction "1_1") (pintype "passive"))
      (node (ref "C2") (pin "1") (pinfunction "1_1") (pintype "passive"))
      (node (ref "C3") (pin "1") (pinfunction "1_1") (pintype "passive"))
      (node (ref "C4") (pin "1") (pinfunction "1_1") (pintype "passive"))
      (node (ref "C7") (pin "1") (pinfunction "1_1") (pintype "passive"))
      (node (ref "IC2") (pin "27") (pinfunction "AVCC_27") (pintype "power_in"))
      (node (ref "IC2") (pin "5") (pinfunction "VCC_5") (pintype "power_in"))
      (node (ref "IC3") (pin "8") (pinfunction "VCC_8") (pintype "input"))
      (node (ref "IC4") (pin "8") (pinfunction "VCC_8") (pintype "input"))
      (node (ref "JP1") (pin "2") (pinfunction "2_2") (pintype "passive"))
      (node (ref "R1") (pin "2") (pinfunction "2_2") (pintype "passive"))
      (node (ref "R2") (pin "2") (pinfunction "2_2") (pintype "passive"))
      (node (ref "R5") (pin "1") (pinfunction "1_1") (pintype "passive"))
      (node (ref "R6") (pin "2") (pinfunction "2_2") (pintype "passive"))
      (node (ref "R7") (pin "2") (pinfunction "2_2") (pintype "passive"))
      (node (ref "R8") (pin "2") (pinfunction "2_2") (pintype "passive"))
      (node (ref "SV1") (pin "2") (pinfunction "2_2") (pintype "passive"))
    )
    (net (code "74") (name "X") (class "Default")
      (node (ref "IC4") (pin "6") (pinfunction "A_6") (pintype "input"))
      (node (ref "X1") (pin "7") (pinfunction "7_7") (pintype "passive"))
      (node (ref "X2") (pin "7") (pinfunction "7_7") (pintype "passive"))
    )
    (net (code "75") (name "Y") (class "Default")
      (node (ref "IC4") (pin "7") (pinfunction "B_7") (pintype "input"))
      (node (ref "X1") (pin "2") (pinfunction "2_2") (pintype "passive"))
      (node (ref "X2") (pin "2") (pinfunction "2_2") (pintype "passive"))
    )
    (net (code "76") (name "unconnected-(IC2-(SS)PB4-Pad44)") (class "Default")
      (node (ref "IC2") (pin "44") (pinfunction "(SS)PB4_44") (pintype "bidirectional"))
    )
    (net (code "77") (name "unconnected-(IC2-(TOSC1)PC6-Pad25)") (class "Default")
      (node (ref "IC2") (pin "25") (pinfunction "(TOSC1)PC6_25") (pintype "bidirectional"))
    )
    (net (code "78") (name "unconnected-(IC2-(TOSC2)PC7-Pad26)") (class "Default")
      (node (ref "IC2") (pin "26") (pinfunction "(TOSC2)PC7_26") (pintype "bidirectional"))
    )
    (net (code "79") (name "unconnected-(IC14-EN-Pad2)") (class "Default")
      (node (ref "IC14") (pin "2") (pinfunction "EN_2") (pintype "input"))
    )
    (net (code "80") (name "unconnected-(X1-Pad5)") (class "Default")
      (node (ref "X1") (pin "5") (pinfunction "5_5") (pintype "passive"))
    )
    (net (code "81") (name "unconnected-(X2-Pad5)") (class "Default")
      (node (ref "X2") (pin "5") (pinfunction "5_5") (pintype "passive"))
    )
  )
)
